# DI_220V_DC.net
KiCad netlist of a schematic drawn in Altium Designer
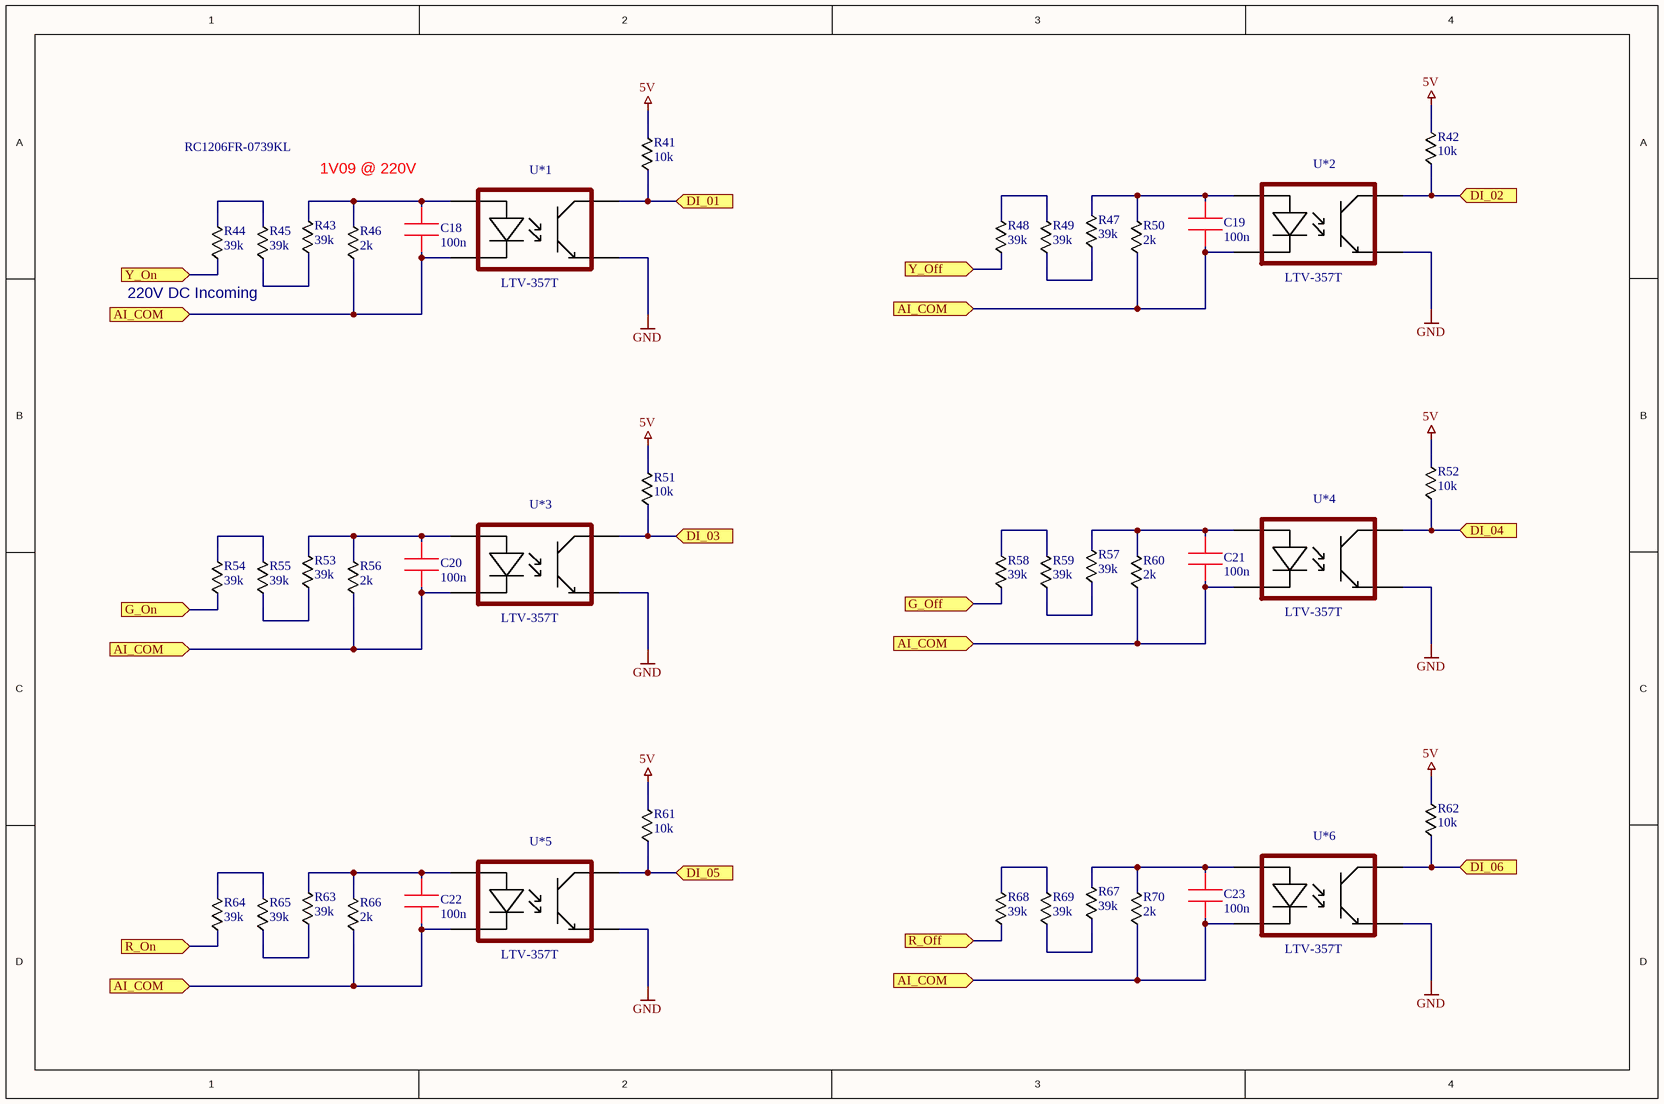
[diagram p0: DI 220V DC.SchDoc]

(export (version "E")
  (design (tool "Eeschema 10.0.6"))
  (components
    (comp (ref "C18")
      (value "100n")
      (footprint "0603")
      (description "CC0603KRX7R9BB104")
      (libsource (lib "kontr") (part "0603 CAP"))
    )
    (comp (ref "C19")
      (value "100n")
      (footprint "0603")
      (description "CC0603KRX7R9BB104")
      (libsource (lib "kontr") (part "0603 CAP"))
    )
    (comp (ref "C20")
      (value "100n")
      (footprint "0603")
      (description "CC0603KRX7R9BB104")
      (libsource (lib "kontr") (part "0603 CAP"))
    )
    (comp (ref "C21")
      (value "100n")
      (footprint "0603")
      (description "CC0603KRX7R9BB104")
      (libsource (lib "kontr") (part "0603 CAP"))
    )
    (comp (ref "C22")
      (value "100n")
      (footprint "0603")
      (description "CC0603KRX7R9BB104")
      (libsource (lib "kontr") (part "0603 CAP"))
    )
    (comp (ref "C23")
      (value "100n")
      (footprint "0603")
      (description "CC0603KRX7R9BB104")
      (libsource (lib "kontr") (part "0603 CAP"))
    )
    (comp (ref "R41")
      (value "10k")
      (footprint "0603")
      (description "RC0603FR-0710KL")
      (libsource (lib "kontr") (part "0603 RES"))
    )
    (comp (ref "R42")
      (value "10k")
      (footprint "0603")
      (description "RC0603FR-0710KL")
      (libsource (lib "kontr") (part "0603 RES"))
    )
    (comp (ref "R43")
      (value "39k")
      (footprint "1206")
      (description "RC1206FR-0739KL")
      (libsource (lib "kontr") (part "1206 R"))
    )
    (comp (ref "R44")
      (value "39k")
      (footprint "1206")
      (description "RC1206FR-0739KL")
      (libsource (lib "kontr") (part "1206 R"))
    )
    (comp (ref "R45")
      (value "39k")
      (footprint "1206")
      (description "RC1206FR-0739KL")
      (libsource (lib "kontr") (part "1206 R"))
    )
    (comp (ref "R46")
      (value "2k")
      (footprint "1206")
      (description "RC1206FR-072KL")
      (libsource (lib "kontr") (part "1206 R"))
    )
    (comp (ref "R47")
      (value "39k")
      (footprint "1206")
      (description "RC1206FR-0739KL")
      (libsource (lib "kontr") (part "1206 R"))
    )
    (comp (ref "R48")
      (value "39k")
      (footprint "1206")
      (description "RC1206FR-0739KL")
      (libsource (lib "kontr") (part "1206 R"))
    )
    (comp (ref "R49")
      (value "39k")
      (footprint "1206")
      (description "RC1206FR-0739KL")
      (libsource (lib "kontr") (part "1206 R"))
    )
    (comp (ref "R50")
      (value "2k")
      (footprint "1206")
      (description "RC1206FR-072KL")
      (libsource (lib "kontr") (part "1206 R"))
    )
    (comp (ref "R51")
      (value "10k")
      (footprint "0603")
      (description "RC0603FR-0710KL")
      (libsource (lib "kontr") (part "0603 RES"))
    )
    (comp (ref "R52")
      (value "10k")
      (footprint "0603")
      (description "RC0603FR-0710KL")
      (libsource (lib "kontr") (part "0603 RES"))
    )
    (comp (ref "R53")
      (value "39k")
      (footprint "1206")
      (description "RC1206FR-0739KL")
      (libsource (lib "kontr") (part "1206 R"))
    )
    (comp (ref "R54")
      (value "39k")
      (footprint "1206")
      (description "RC1206FR-0739KL")
      (libsource (lib "kontr") (part "1206 R"))
    )
    (comp (ref "R55")
      (value "39k")
      (footprint "1206")
      (description "RC1206FR-0739KL")
      (libsource (lib "kontr") (part "1206 R"))
    )
    (comp (ref "R56")
      (value "2k")
      (footprint "1206")
      (description "RC1206FR-072KL")
      (libsource (lib "kontr") (part "1206 R"))
    )
    (comp (ref "R57")
      (value "39k")
      (footprint "1206")
      (description "RC1206FR-0739KL")
      (libsource (lib "kontr") (part "1206 R"))
    )
    (comp (ref "R58")
      (value "39k")
      (footprint "1206")
      (description "RC1206FR-0739KL")
      (libsource (lib "kontr") (part "1206 R"))
    )
    (comp (ref "R59")
      (value "39k")
      (footprint "1206")
      (description "RC1206FR-0739KL")
      (libsource (lib "kontr") (part "1206 R"))
    )
    (comp (ref "R60")
      (value "2k")
      (footprint "1206")
      (description "RC1206FR-072KL")
      (libsource (lib "kontr") (part "1206 R"))
    )
    (comp (ref "R61")
      (value "10k")
      (footprint "0603")
      (description "RC0603FR-0710KL")
      (libsource (lib "kontr") (part "0603 RES"))
    )
    (comp (ref "R62")
      (value "10k")
      (footprint "0603")
      (description "RC0603FR-0710KL")
      (libsource (lib "kontr") (part "0603 RES"))
    )
    (comp (ref "R63")
      (value "39k")
      (footprint "1206")
      (description "RC1206FR-0739KL")
      (libsource (lib "kontr") (part "1206 R"))
    )
    (comp (ref "R64")
      (value "39k")
      (footprint "1206")
      (description "RC1206FR-0739KL")
      (libsource (lib "kontr") (part "1206 R"))
    )
    (comp (ref "R65")
      (value "39k")
      (footprint "1206")
      (description "RC1206FR-0739KL")
      (libsource (lib "kontr") (part "1206 R"))
    )
    (comp (ref "R66")
      (value "2k")
      (footprint "1206")
      (description "RC1206FR-072KL")
      (libsource (lib "kontr") (part "1206 R"))
    )
    (comp (ref "R67")
      (value "39k")
      (footprint "1206")
      (description "RC1206FR-0739KL")
      (libsource (lib "kontr") (part "1206 R"))
    )
    (comp (ref "R68")
      (value "39k")
      (footprint "1206")
      (description "RC1206FR-0739KL")
      (libsource (lib "kontr") (part "1206 R"))
    )
    (comp (ref "R69")
      (value "39k")
      (footprint "1206")
      (description "RC1206FR-0739KL")
      (libsource (lib "kontr") (part "1206 R"))
    )
    (comp (ref "R70")
      (value "2k")
      (footprint "1206")
      (description "RC1206FR-072KL")
      (libsource (lib "kontr") (part "1206 R"))
    )
    (comp (ref "U*1") (value "LTV-357T") (footprint "SOP-4") (libsource (lib "levin") (part "LTV-357T")))
    (comp (ref "U*2") (value "LTV-357T") (footprint "SOP-4") (libsource (lib "levin") (part "LTV-357T")))
    (comp (ref "U*3") (value "LTV-357T") (footprint "SOP-4") (libsource (lib "levin") (part "LTV-357T")))
    (comp (ref "U*4") (value "LTV-357T") (footprint "SOP-4") (libsource (lib "levin") (part "LTV-357T")))
    (comp (ref "U*5") (value "LTV-357T") (footprint "SOP-4") (libsource (lib "levin") (part "LTV-357T")))
    (comp (ref "U*6") (value "LTV-357T") (footprint "SOP-4") (libsource (lib "levin") (part "LTV-357T")))
  )
  (nets
    (net (code "1") (name "/AI_COM") (class "Default")
      (node (ref "C18") (pin "1") (pinfunction "1_1") (pintype "passive"))
      (node (ref "C19") (pin "1") (pinfunction "1_1") (pintype "passive"))
      (node (ref "C20") (pin "1") (pinfunction "1_1") (pintype "passive"))
      (node (ref "C21") (pin "1") (pinfunction "1_1") (pintype "passive"))
      (node (ref "C22") (pin "1") (pinfunction "1_1") (pintype "passive"))
      (node (ref "C23") (pin "1") (pinfunction "1_1") (pintype "passive"))
      (node (ref "R46") (pin "1") (pintype "passive"))
      (node (ref "R50") (pin "1") (pintype "passive"))
      (node (ref "R56") (pin "1") (pintype "passive"))
      (node (ref "R60") (pin "1") (pintype "passive"))
      (node (ref "R66") (pin "1") (pintype "passive"))
      (node (ref "R70") (pin "1") (pintype "passive"))
      (node (ref "U*1") (pin "Cathode") (pinfunction "C_Cathode") (pintype "passive"))
      (node (ref "U*2") (pin "Cathode") (pinfunction "C_Cathode") (pintype "passive"))
      (node (ref "U*3") (pin "Cathode") (pinfunction "C_Cathode") (pintype "passive"))
      (node (ref "U*4") (pin "Cathode") (pinfunction "C_Cathode") (pintype "passive"))
      (node (ref "U*5") (pin "Cathode") (pinfunction "C_Cathode") (pintype "passive"))
      (node (ref "U*6") (pin "Cathode") (pinfunction "C_Cathode") (pintype "passive"))
    )
    (net (code "2") (name "/DI_01") (class "Default")
      (node (ref "R41") (pin "1") (pintype "passive"))
      (node (ref "U*1") (pin "Collector") (pinfunction "C_Collector") (pintype "passive"))
    )
    (net (code "3") (name "/DI_02") (class "Default")
      (node (ref "R42") (pin "1") (pintype "passive"))
      (node (ref "U*2") (pin "Collector") (pinfunction "C_Collector") (pintype "passive"))
    )
    (net (code "4") (name "/DI_03") (class "Default")
      (node (ref "R51") (pin "1") (pintype "passive"))
      (node (ref "U*3") (pin "Collector") (pinfunction "C_Collector") (pintype "passive"))
    )
    (net (code "5") (name "/DI_04") (class "Default")
      (node (ref "R52") (pin "1") (pintype "passive"))
      (node (ref "U*4") (pin "Collector") (pinfunction "C_Collector") (pintype "passive"))
    )
    (net (code "6") (name "/DI_05") (class "Default")
      (node (ref "R61") (pin "1") (pintype "passive"))
      (node (ref "U*5") (pin "Collector") (pinfunction "C_Collector") (pintype "passive"))
    )
    (net (code "7") (name "/DI_06") (class "Default")
      (node (ref "R62") (pin "1") (pintype "passive"))
      (node (ref "U*6") (pin "Collector") (pinfunction "C_Collector") (pintype "passive"))
    )
    (net (code "8") (name "/G_Off") (class "Default") (node (ref "R58") (pin "1") (pintype "passive")))
    (net (code "9") (name "/G_On") (class "Default") (node (ref "R54") (pin "1") (pintype "passive")))
    (net (code "10") (name "/R_Off") (class "Default") (node (ref "R68") (pin "1") (pintype "passive")))
    (net (code "11") (name "/R_On") (class "Default") (node (ref "R64") (pin "1") (pintype "passive")))
    (net (code "12") (name "/Y_Off") (class "Default") (node (ref "R48") (pin "1") (pintype "passive")))
    (net (code "13") (name "/Y_On") (class "Default") (node (ref "R44") (pin "1") (pintype "passive")))
    (net (code "14") (name "5V") (class "Default")
      (node (ref "R41") (pin "2") (pintype "passive"))
      (node (ref "R42") (pin "2") (pintype "passive"))
      (node (ref "R51") (pin "2") (pintype "passive"))
      (node (ref "R52") (pin "2") (pintype "passive"))
      (node (ref "R61") (pin "2") (pintype "passive"))
      (node (ref "R62") (pin "2") (pintype "passive"))
    )
    (net (code "15") (name "GND") (class "Default")
      (node (ref "U*1") (pin "Emmiter") (pinfunction "E_Emmiter") (pintype "passive"))
      (node (ref "U*2") (pin "Emmiter") (pinfunction "E_Emmiter") (pintype "passive"))
      (node (ref "U*3") (pin "Emmiter") (pinfunction "E_Emmiter") (pintype "passive"))
      (node (ref "U*4") (pin "Emmiter") (pinfunction "E_Emmiter") (pintype "passive"))
      (node (ref "U*5") (pin "Emmiter") (pinfunction "E_Emmiter") (pintype "passive"))
      (node (ref "U*6") (pin "Emmiter") (pinfunction "E_Emmiter") (pintype "passive"))
    )
    (net (code "16") (name "Net-(R43-Pad1)") (class "Default")
      (node (ref "R43") (pin "1") (pintype "passive"))
      (node (ref "R45") (pin "1") (pintype "passive"))
    )
    (net (code "17") (name "Net-(R44-Pad2)") (class "Default")
      (node (ref "R44") (pin "2") (pintype "passive"))
      (node (ref "R45") (pin "2") (pintype "passive"))
    )
    (net (code "18") (name "Net-(R47-Pad1)") (class "Default")
      (node (ref "R47") (pin "1") (pintype "passive"))
      (node (ref "R49") (pin "1") (pintype "passive"))
    )
    (net (code "19") (name "Net-(R48-Pad2)") (class "Default")
      (node (ref "R48") (pin "2") (pintype "passive"))
      (node (ref "R49") (pin "2") (pintype "passive"))
    )
    (net (code "20") (name "Net-(R53-Pad1)") (class "Default")
      (node (ref "R53") (pin "1") (pintype "passive"))
      (node (ref "R55") (pin "1") (pintype "passive"))
    )
    (net (code "21") (name "Net-(R54-Pad2)") (class "Default")
      (node (ref "R54") (pin "2") (pintype "passive"))
      (node (ref "R55") (pin "2") (pintype "passive"))
    )
    (net (code "22") (name "Net-(R57-Pad1)") (class "Default")
      (node (ref "R57") (pin "1") (pintype "passive"))
      (node (ref "R59") (pin "1") (pintype "passive"))
    )
    (net (code "23") (name "Net-(R58-Pad2)") (class "Default")
      (node (ref "R58") (pin "2") (pintype "passive"))
      (node (ref "R59") (pin "2") (pintype "passive"))
    )
    (net (code "24") (name "Net-(R63-Pad1)") (class "Default")
      (node (ref "R63") (pin "1") (pintype "passive"))
      (node (ref "R65") (pin "1") (pintype "passive"))
    )
    (net (code "25") (name "Net-(R64-Pad2)") (class "Default")
      (node (ref "R64") (pin "2") (pintype "passive"))
      (node (ref "R65") (pin "2") (pintype "passive"))
    )
    (net (code "26") (name "Net-(R67-Pad1)") (class "Default")
      (node (ref "R67") (pin "1") (pintype "passive"))
      (node (ref "R69") (pin "1") (pintype "passive"))
    )
    (net (code "27") (name "Net-(R68-Pad2)") (class "Default")
      (node (ref "R68") (pin "2") (pintype "passive"))
      (node (ref "R69") (pin "2") (pintype "passive"))
    )
    (net (code "28") (name "Net-(U*1-A)") (class "Default")
      (node (ref "C18") (pin "2") (pinfunction "2_2") (pintype "passive"))
      (node (ref "R43") (pin "2") (pintype "passive"))
      (node (ref "R46") (pin "2") (pintype "passive"))
      (node (ref "U*1") (pin "Anode") (pinfunction "A_Anode") (pintype "passive"))
    )
    (net (code "29") (name "Net-(U*2-A)") (class "Default")
      (node (ref "C19") (pin "2") (pinfunction "2_2") (pintype "passive"))
      (node (ref "R47") (pin "2") (pintype "passive"))
      (node (ref "R50") (pin "2") (pintype "passive"))
      (node (ref "U*2") (pin "Anode") (pinfunction "A_Anode") (pintype "passive"))
    )
    (net (code "30") (name "Net-(U*3-A)") (class "Default")
      (node (ref "C20") (pin "2") (pinfunction "2_2") (pintype "passive"))
      (node (ref "R53") (pin "2") (pintype "passive"))
      (node (ref "R56") (pin "2") (pintype "passive"))
      (node (ref "U*3") (pin "Anode") (pinfunction "A_Anode") (pintype "passive"))
    )
    (net (code "31") (name "Net-(U*4-A)") (class "Default")
      (node (ref "C21") (pin "2") (pinfunction "2_2") (pintype "passive"))
      (node (ref "R57") (pin "2") (pintype "passive"))
      (node (ref "R60") (pin "2") (pintype "passive"))
      (node (ref "U*4") (pin "Anode") (pinfunction "A_Anode") (pintype "passive"))
    )
    (net (code "32") (name "Net-(U*5-A)") (class "Default")
      (node (ref "C22") (pin "2") (pinfunction "2_2") (pintype "passive"))
      (node (ref "R63") (pin "2") (pintype "passive"))
      (node (ref "R66") (pin "2") (pintype "passive"))
      (node (ref "U*5") (pin "Anode") (pinfunction "A_Anode") (pintype "passive"))
    )
    (net (code "33") (name "Net-(U*6-A)") (class "Default")
      (node (ref "C23") (pin "2") (pinfunction "2_2") (pintype "passive"))
      (node (ref "R67") (pin "2") (pintype "passive"))
      (node (ref "R70") (pin "2") (pintype "passive"))
      (node (ref "U*6") (pin "Anode") (pinfunction "A_Anode") (pintype "passive"))
    )
  )
)
